# Schematic_3.net
KiCad netlist of a schematic drawn in Altium Designer
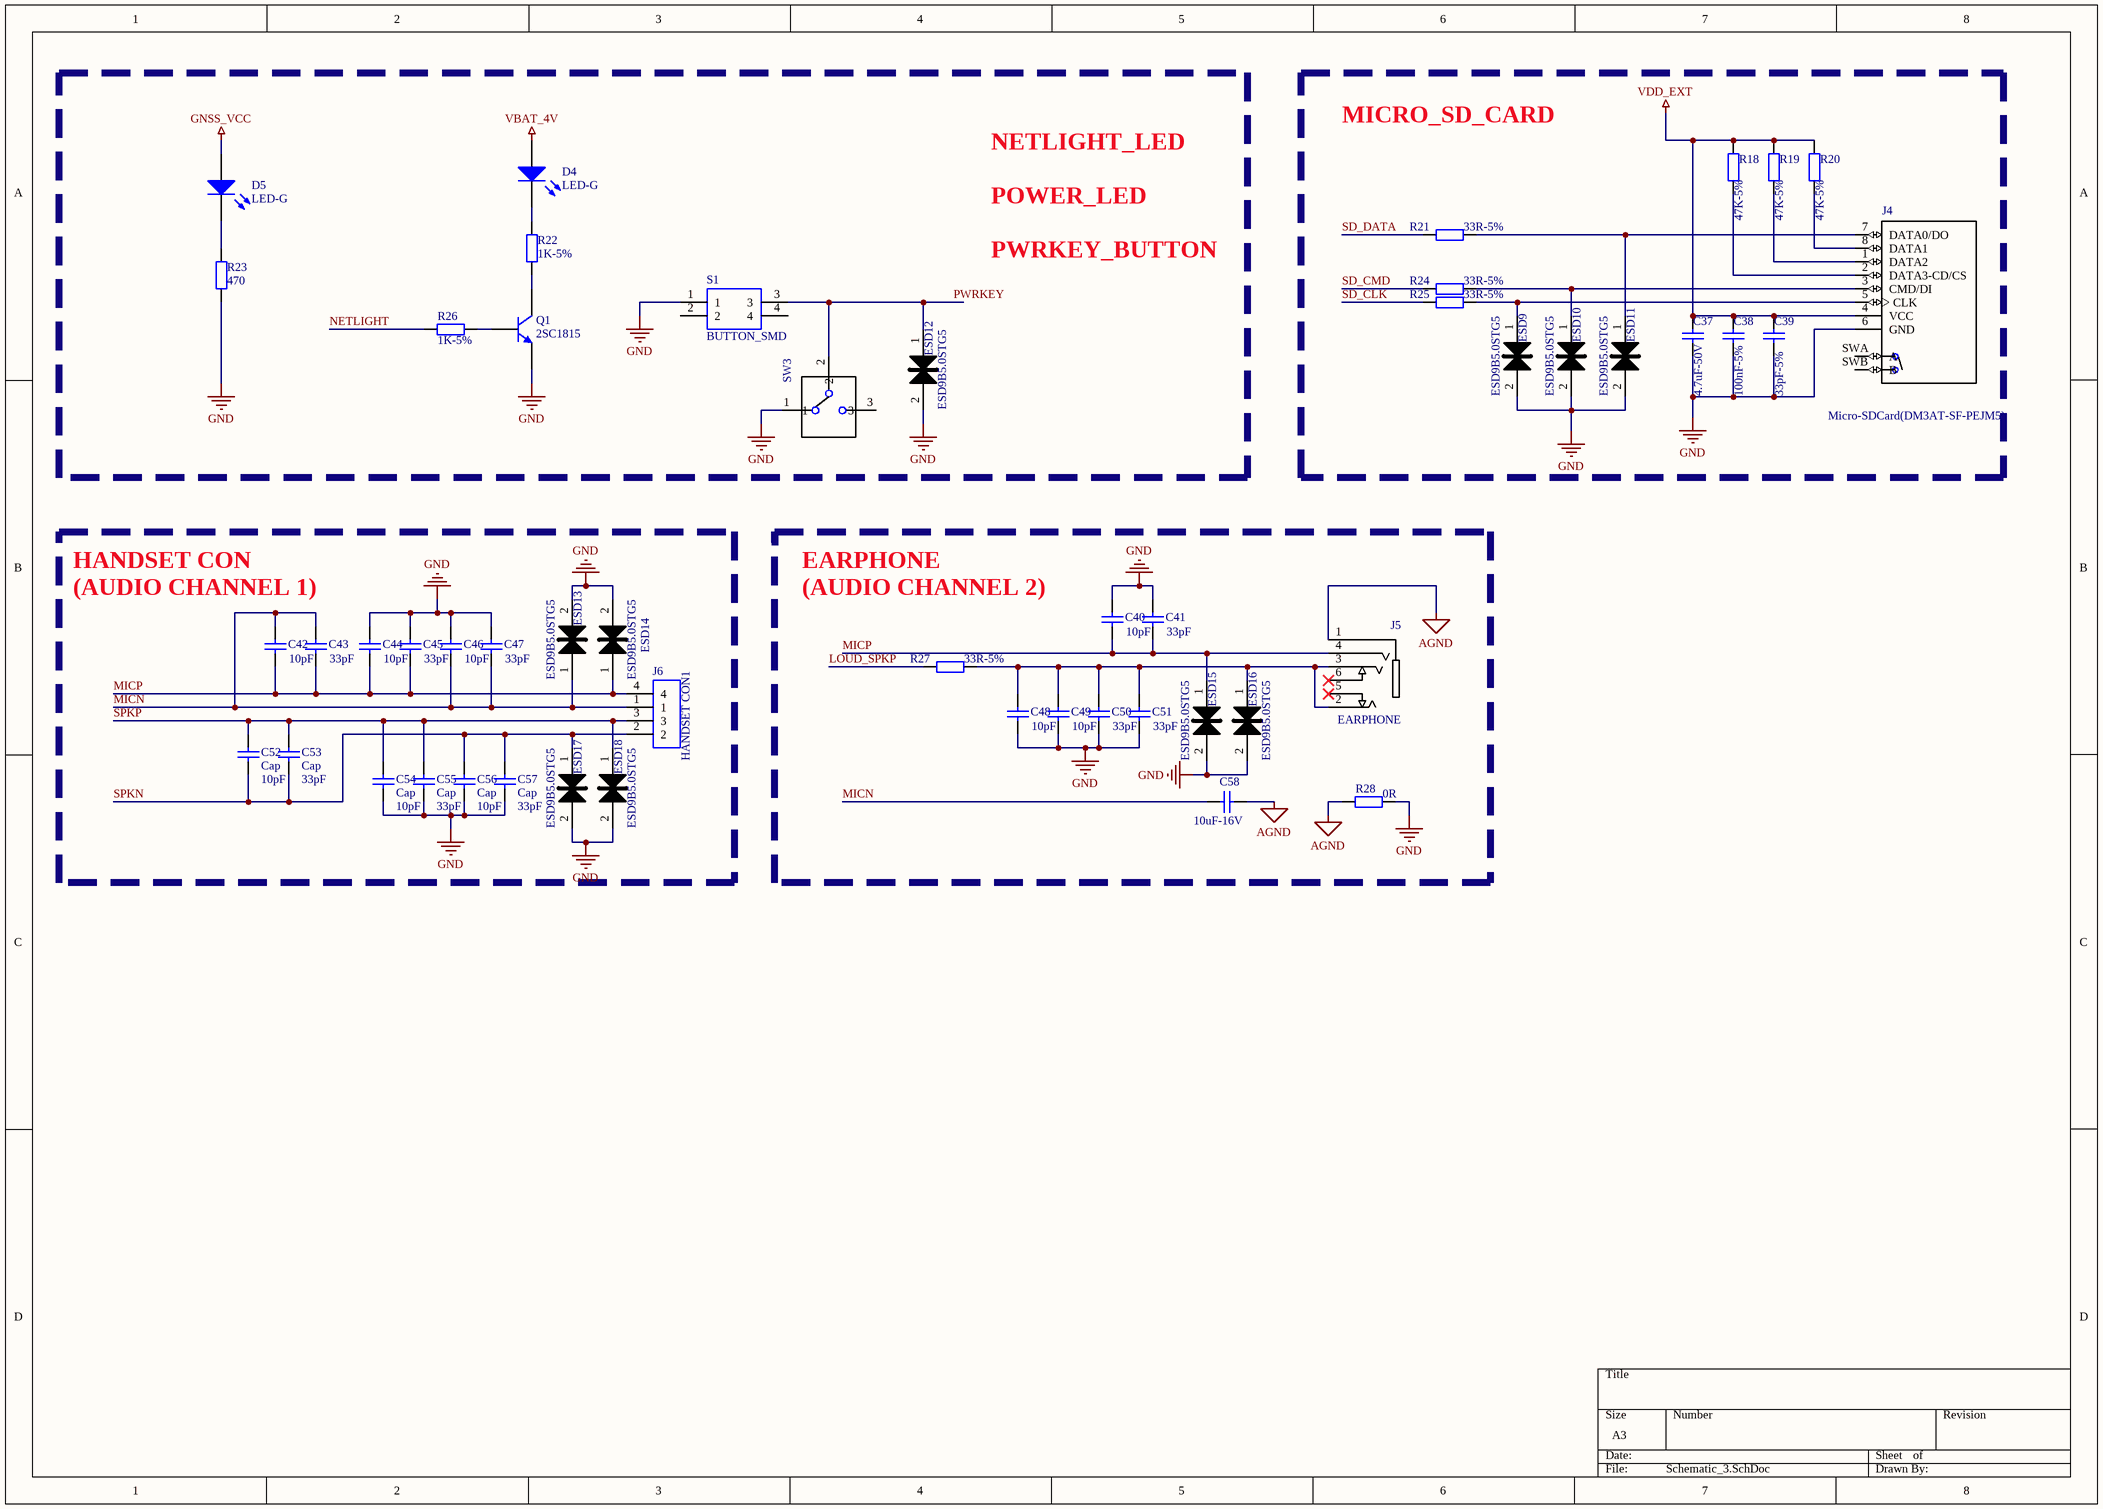
[diagram p0: Schematic_3.SchDoc]

(export (version "E")
  (design (tool "Eeschema 10.0.6"))
  (components
    (comp (ref "C37")
      (value "4.7uF-50V")
      (footprint "C0805")
      (description "Capacitor")
      (fields (field (name "Comment") "Cap") (field (name "PUBLISHER") "Altium Limited"))
      (libsource (lib "Miscellaneous Devices") (part "Cap"))
    )
    (comp (ref "C38")
      (value "100nF-5%")
      (footprint "C0805")
      (description "Capacitor")
      (fields (field (name "Comment") "Cap") (field (name "PUBLISHER") "Altium Limited"))
      (libsource (lib "Miscellaneous Devices") (part "Cap"))
    )
    (comp (ref "C39")
      (value "33pF-5%")
      (footprint "C0805")
      (description "Capacitor")
      (fields (field (name "Comment") "Cap") (field (name "PUBLISHER") "Altium Limited"))
      (libsource (lib "Miscellaneous Devices") (part "Cap"))
    )
    (comp (ref "C40")
      (value "10pF")
      (footprint "C0805")
      (description "Capacitor")
      (fields (field (name "Comment") "Cap") (field (name "PUBLISHER") "Altium Limited"))
      (libsource (lib "Miscellaneous Devices") (part "Cap"))
    )
    (comp (ref "C41")
      (value "33pF")
      (footprint "C0805")
      (description "Capacitor")
      (fields (field (name "Comment") "Cap") (field (name "PUBLISHER") "Altium Limited"))
      (libsource (lib "Miscellaneous Devices") (part "Cap"))
    )
    (comp (ref "C42")
      (value "10pF")
      (footprint "C0805")
      (description "Capacitor")
      (fields (field (name "Comment") "Cap") (field (name "PUBLISHER") "Altium Limited"))
      (libsource (lib "Miscellaneous Devices") (part "Cap"))
    )
    (comp (ref "C43")
      (value "33pF")
      (footprint "C0805")
      (description "Capacitor")
      (fields (field (name "Comment") "Cap") (field (name "PUBLISHER") "Altium Limited"))
      (libsource (lib "Miscellaneous Devices") (part "Cap"))
    )
    (comp (ref "C44")
      (value "10pF")
      (footprint "C0805")
      (description "Capacitor")
      (fields (field (name "Comment") "Cap") (field (name "PUBLISHER") "Altium Limited"))
      (libsource (lib "Miscellaneous Devices") (part "Cap"))
    )
    (comp (ref "C45")
      (value "33pF")
      (footprint "C0805")
      (description "Capacitor")
      (fields (field (name "Comment") "Cap") (field (name "PUBLISHER") "Altium Limited"))
      (libsource (lib "Miscellaneous Devices") (part "Cap"))
    )
    (comp (ref "C46")
      (value "10pF")
      (footprint "C0805")
      (description "Capacitor")
      (fields (field (name "Comment") "Cap") (field (name "PUBLISHER") "Altium Limited"))
      (libsource (lib "Miscellaneous Devices") (part "Cap"))
    )
    (comp (ref "C47")
      (value "33pF")
      (footprint "C0805")
      (description "Capacitor")
      (fields (field (name "Comment") "Cap") (field (name "PUBLISHER") "Altium Limited"))
      (libsource (lib "Miscellaneous Devices") (part "Cap"))
    )
    (comp (ref "C48")
      (value "10pF")
      (footprint "C0805")
      (description "Capacitor")
      (fields (field (name "Comment") "Cap") (field (name "PUBLISHER") "Altium Limited"))
      (libsource (lib "Miscellaneous Devices") (part "Cap"))
    )
    (comp (ref "C49")
      (value "10pF")
      (footprint "C0805")
      (description "Capacitor")
      (fields (field (name "Comment") "Cap") (field (name "PUBLISHER") "Altium Limited"))
      (libsource (lib "Miscellaneous Devices") (part "Cap"))
    )
    (comp (ref "C50")
      (value "33pF")
      (footprint "C0805")
      (description "Capacitor")
      (fields (field (name "Comment") "Cap") (field (name "PUBLISHER") "Altium Limited"))
      (libsource (lib "Miscellaneous Devices") (part "Cap"))
    )
    (comp (ref "C51")
      (value "33pF")
      (footprint "C0805")
      (description "Capacitor")
      (fields (field (name "Comment") "Cap") (field (name "PUBLISHER") "Altium Limited"))
      (libsource (lib "Miscellaneous Devices") (part "Cap"))
    )
    (comp (ref "C52")
      (value "Cap")
      (footprint "C0805")
      (description "Capacitor")
      (fields (field (name "ALTIUM_VALUE") "10pF") (field (name "PUBLISHER") "Altium Limited"))
      (libsource (lib "Miscellaneous Devices") (part "Cap"))
    )
    (comp (ref "C53")
      (value "Cap")
      (footprint "C0805")
      (description "Capacitor")
      (fields (field (name "ALTIUM_VALUE") "33pF") (field (name "PUBLISHER") "Altium Limited"))
      (libsource (lib "Miscellaneous Devices") (part "Cap"))
    )
    (comp (ref "C54")
      (value "Cap")
      (footprint "C0805")
      (description "Capacitor")
      (fields (field (name "ALTIUM_VALUE") "10pF") (field (name "PUBLISHER") "Altium Limited"))
      (libsource (lib "Miscellaneous Devices") (part "Cap"))
    )
    (comp (ref "C55")
      (value "Cap")
      (footprint "C0805")
      (description "Capacitor")
      (fields (field (name "ALTIUM_VALUE") "33pF") (field (name "PUBLISHER") "Altium Limited"))
      (libsource (lib "Miscellaneous Devices") (part "Cap"))
    )
    (comp (ref "C56")
      (value "Cap")
      (footprint "C0805")
      (description "Capacitor")
      (fields (field (name "ALTIUM_VALUE") "10pF") (field (name "PUBLISHER") "Altium Limited"))
      (libsource (lib "Miscellaneous Devices") (part "Cap"))
    )
    (comp (ref "C57")
      (value "Cap")
      (footprint "C0805")
      (description "Capacitor")
      (fields (field (name "ALTIUM_VALUE") "33pF") (field (name "PUBLISHER") "Altium Limited"))
      (libsource (lib "Miscellaneous Devices") (part "Cap"))
    )
    (comp (ref "C58")
      (value "10uF-16V")
      (footprint "C0805")
      (description "Capacitor")
      (fields (field (name "Comment") "Cap") (field (name "PUBLISHER") "Altium Limited"))
      (libsource (lib "Miscellaneous Devices") (part "Cap"))
    )
    (comp (ref "D4")
      (value "LED-G")
      (footprint "6-0805_L")
      (description "Typical INFRARED GaAs LED")
      (fields (field (name "PUBLISHER") "Altium Limited"))
      (libsource (lib "Miscellaneous Devices") (part "LED0"))
    )
    (comp (ref "D5")
      (value "LED-G")
      (footprint "6-0805_L")
      (description "Typical INFRARED GaAs LED")
      (fields (field (name "PUBLISHER") "Altium Limited"))
      (libsource (lib "Miscellaneous Devices") (part "LED0"))
    )
    (comp (ref "ESD9")
      (value "ESD9B5.0STG5")
      (footprint "ESD9B5.0STG5")
      (libsource (lib "ESD9B5") (part "1"))
    )
    (comp (ref "ESD10")
      (value "ESD9B5.0STG5")
      (footprint "ESD9B5.0STG5")
      (libsource (lib "ESD9B5") (part "1"))
    )
    (comp (ref "ESD11")
      (value "ESD9B5.0STG5")
      (footprint "ESD9B5.0STG5")
      (libsource (lib "ESD9B5") (part "1"))
    )
    (comp (ref "ESD12")
      (value "ESD9B5.0STG5")
      (footprint "ESD9B5.0STG5")
      (libsource (lib "ESD9B5") (part "1"))
    )
    (comp (ref "ESD13")
      (value "ESD9B5.0STG5")
      (footprint "ESD9B5.0STG5")
      (libsource (lib "ESD9B5") (part "1"))
    )
    (comp (ref "ESD14")
      (value "ESD9B5.0STG5")
      (footprint "ESD9B5.0STG5")
      (libsource (lib "ESD9B5") (part "1"))
    )
    (comp (ref "ESD15")
      (value "ESD9B5.0STG5")
      (footprint "ESD9B5.0STG5")
      (libsource (lib "ESD9B5") (part "1"))
    )
    (comp (ref "ESD16")
      (value "ESD9B5.0STG5")
      (footprint "ESD9B5.0STG5")
      (libsource (lib "ESD9B5") (part "1"))
    )
    (comp (ref "ESD17")
      (value "ESD9B5.0STG5")
      (footprint "ESD9B5.0STG5")
      (libsource (lib "ESD9B5") (part "1"))
    )
    (comp (ref "ESD18")
      (value "ESD9B5.0STG5")
      (footprint "ESD9B5.0STG5")
      (libsource (lib "ESD9B5") (part "1"))
    )
    (comp (ref "J4")
      (value "Micro-SDCard(DM3AT-SF-PEJM5)")
      (footprint "SD_CARD")
      (description "DM3 RA SMT microSD memory card push/push")
      (fields (field (name "MP") "DM3AT-SF-PEJM5") (field (name "MF") "Hirose"))
      (libsource (lib "DM3AT-SF-PEJM5") (part "DM3AT-SF-PEJM5"))
    )
    (comp (ref "J5")
      (value "EARPHONE")
      (footprint "Audio_Jack")
      (description "audio jack, 3.5 mm, rt, 4 conductor, mid mount SMT, 2 switches, T/R package")
      (fields (field (name "MF") "CUI") (field (name "MP") "SJ-43504-SMT-TR"))
      (libsource (lib "SJ-43504-SMT-TR") (part "SJ-43504-SMT-TR"))
    )
    (comp (ref "J6")
      (value "HANDSET CON1")
      (footprint "RJ11-HANDSETCON")
      (fields
        (field (name "MANUFACTURER_PART_NUMBER") "95009-7441")
        (field (name "RS PART NUMBER") "8967548")
      )
      (libsource (lib "95009-7441") (part "95009-7441"))
    )
    (comp (ref "Q1")
      (value "2SC1815")
      (footprint "SOT23_L")
      (description "NPN General Purpose Amplifier")
      (fields (field (name "PUBLISHER") "Altium Limited"))
      (libsource (lib "Miscellaneous Devices") (part "2N3904"))
    )
    (comp (ref "R18")
      (value "47K-5%")
      (footprint "6-0805_L")
      (description "Resistor")
      (fields (field (name "Comment") "Res2") (field (name "PUBLISHER") "Altium Limited"))
      (libsource (lib "Miscellaneous Devices") (part "Res2"))
    )
    (comp (ref "R19")
      (value "47K-5%")
      (footprint "6-0805_L")
      (description "Resistor")
      (fields (field (name "Comment") "Res2") (field (name "PUBLISHER") "Altium Limited"))
      (libsource (lib "Miscellaneous Devices") (part "Res2"))
    )
    (comp (ref "R20")
      (value "47K-5%")
      (footprint "6-0805_L")
      (description "Resistor")
      (fields (field (name "Comment") "Res2") (field (name "PUBLISHER") "Altium Limited"))
      (libsource (lib "Miscellaneous Devices") (part "Res2"))
    )
    (comp (ref "R21")
      (value "33R-5%")
      (footprint "6-0805_L")
      (description "Resistor")
      (fields (field (name "Comment") "Res2") (field (name "PUBLISHER") "Altium Limited"))
      (libsource (lib "") (part "Res2_1"))
    )
    (comp (ref "R22")
      (value "1K-5%")
      (footprint "6-0805_L")
      (description "Resistor")
      (fields (field (name "Comment") "Res2") (field (name "PUBLISHER") "Altium Limited"))
      (libsource (lib "") (part "Res2_2"))
    )
    (comp (ref "R23")
      (value "470")
      (footprint "6-0805_L")
      (description "Resistor")
      (fields (field (name "Comment") "Res2") (field (name "PUBLISHER") "Altium Limited"))
      (libsource (lib "") (part "Res2_2"))
    )
    (comp (ref "R24")
      (value "33R-5%")
      (footprint "6-0805_L")
      (description "Resistor")
      (fields (field (name "Comment") "Res2") (field (name "PUBLISHER") "Altium Limited"))
      (libsource (lib "") (part "Res2_1"))
    )
    (comp (ref "R25")
      (value "33R-5%")
      (footprint "6-0805_L")
      (description "Resistor")
      (fields (field (name "Comment") "Res2") (field (name "PUBLISHER") "Altium Limited"))
      (libsource (lib "") (part "Res2_1"))
    )
    (comp (ref "R26")
      (value "1K-5%")
      (footprint "6-0805_L")
      (description "Resistor")
      (fields (field (name "Comment") "Res2") (field (name "PUBLISHER") "Altium Limited"))
      (libsource (lib "") (part "Res2_3"))
    )
    (comp (ref "R27")
      (value "33R-5%")
      (footprint "6-0805_L")
      (description "Resistor")
      (fields (field (name "Comment") "Res2") (field (name "PUBLISHER") "Altium Limited"))
      (libsource (lib "") (part "Res2_1"))
    )
    (comp (ref "R28")
      (value "0R")
      (footprint "6-0805_L")
      (description "Resistor")
      (fields (field (name "Comment") "Res2") (field (name "PUBLISHER") "Altium Limited"))
      (libsource (lib "") (part "Res2_1"))
    )
    (comp (ref "S1")
      (value "BUTTON_SMD")
      (footprint "BUTTON_4PINS_SMD_3D")
      (description "6x6mm SMD tactile switch,5mm H 1.6N Black Button Tactile Switch, SPST-NO 0.05 A@ 12 V dc 1.4mm")
      (fields
        (field (name "MANUFACTURER_PART_NUMBER") "4-1437565-1")
        (field (name "RS PART NUMBER") "1616046")
      )
      (libsource (lib "4-1437565-1") (part "4-1437565-1"))
    )
    (comp (ref "SW3")
      (value "DIP-SLIDE-SWITCH(3P-11.6X4.0X5.4+2.0MM)")
      (footprint "SLIDE_SWITCH_3PINS")
      (description "EG Series SPDT On-On Vertical Through Hole Slide Switch")
      (fields (field (name "MF") "E-Switch") (field (name "MP") "EG1218"))
      (libsource (lib "DIP-SLIDE-SWITCH_3P-11.6X4.0X5.4_2.0MM_") (part "DIP-SLIDE-SWITCH(3P-11.6X4.0X5.4+2.0MM)"))
    )
  )
  (nets
    (net (code "1") (name "/LOUD_SPKP") (class "Default")
      (node (ref "R27") (pin "1") (pinfunction "1_1") (pintype "passive"))
    )
    (net (code "2") (name "/MICN") (class "Default")
      (node (ref "C42") (pin "2") (pinfunction "2_2") (pintype "passive"))
      (node (ref "C43") (pin "2") (pinfunction "2_2") (pintype "passive"))
      (node (ref "C46") (pin "1") (pinfunction "1_1") (pintype "passive"))
      (node (ref "C47") (pin "1") (pinfunction "1_1") (pintype "passive"))
      (node (ref "C58") (pin "1") (pinfunction "1_1") (pintype "passive"))
      (node (ref "ESD13") (pin "1") (pinfunction "A_1") (pintype "passive"))
      (node (ref "J6") (pin "1") (pinfunction "1_1") (pintype "passive"))
    )
    (net (code "3") (name "/MICP") (class "Default")
      (node (ref "C40") (pin "2") (pinfunction "2_2") (pintype "passive"))
      (node (ref "C41") (pin "2") (pinfunction "2_2") (pintype "passive"))
      (node (ref "C42") (pin "1") (pinfunction "1_1") (pintype "passive"))
      (node (ref "C43") (pin "1") (pinfunction "1_1") (pintype "passive"))
      (node (ref "C44") (pin "1") (pinfunction "1_1") (pintype "passive"))
      (node (ref "C45") (pin "1") (pinfunction "1_1") (pintype "passive"))
      (node (ref "ESD14") (pin "1") (pinfunction "A_1") (pintype "passive"))
      (node (ref "ESD15") (pin "1") (pinfunction "A_1") (pintype "passive"))
      (node (ref "J5") (pin "4") (pinfunction "RING2_4") (pintype "passive"))
      (node (ref "J6") (pin "4") (pinfunction "4_4") (pintype "passive"))
    )
    (net (code "4") (name "/NETLIGHT") (class "Default")
      (node (ref "R26") (pin "2") (pinfunction "2_2") (pintype "passive"))
    )
    (net (code "5") (name "/PWRKEY") (class "Default")
      (node (ref "ESD12") (pin "1") (pinfunction "A_1") (pintype "passive"))
      (node (ref "S1") (pin "3") (pinfunction "3_3") (pintype "passive"))
      (node (ref "SW3") (pin "2") (pinfunction "2_2") (pintype "bidirectional"))
    )
    (net (code "6") (name "/SD_CLK") (class "Default")
      (node (ref "R25") (pin "1") (pinfunction "1_1") (pintype "passive"))
    )
    (net (code "7") (name "/SD_CMD") (class "Default")
      (node (ref "R24") (pin "1") (pinfunction "1_1") (pintype "passive"))
    )
    (net (code "8") (name "/SD_DATA") (class "Default")
      (node (ref "R21") (pin "1") (pinfunction "1_1") (pintype "passive"))
    )
    (net (code "9") (name "/SPKN") (class "Default")
      (node (ref "C52") (pin "1") (pinfunction "1_1") (pintype "passive"))
      (node (ref "C53") (pin "1") (pinfunction "1_1") (pintype "passive"))
      (node (ref "C56") (pin "2") (pinfunction "2_2") (pintype "passive"))
      (node (ref "C57") (pin "2") (pinfunction "2_2") (pintype "passive"))
      (node (ref "ESD17") (pin "1") (pinfunction "A_1") (pintype "passive"))
      (node (ref "J6") (pin "2") (pinfunction "2_2") (pintype "passive"))
    )
    (net (code "10") (name "/SPKP") (class "Default")
      (node (ref "C52") (pin "2") (pinfunction "2_2") (pintype "passive"))
      (node (ref "C53") (pin "2") (pinfunction "2_2") (pintype "passive"))
      (node (ref "C54") (pin "2") (pinfunction "2_2") (pintype "passive"))
      (node (ref "C55") (pin "2") (pinfunction "2_2") (pintype "passive"))
      (node (ref "ESD18") (pin "1") (pinfunction "A_1") (pintype "passive"))
      (node (ref "J6") (pin "3") (pinfunction "3_3") (pintype "passive"))
    )
    (net (code "11") (name "AGND") (class "Default")
      (node (ref "C58") (pin "2") (pinfunction "2_2") (pintype "passive"))
      (node (ref "J5") (pin "1") (pinfunction "SLEEVE_1") (pintype "passive"))
      (node (ref "R28") (pin "1") (pinfunction "1_1") (pintype "passive"))
    )
    (net (code "12") (name "GND") (class "Default")
      (node (ref "C37") (pin "1") (pinfunction "1_1") (pintype "passive"))
      (node (ref "C38") (pin "1") (pinfunction "1_1") (pintype "passive"))
      (node (ref "C39") (pin "2") (pinfunction "2_2") (pintype "passive"))
      (node (ref "C40") (pin "1") (pinfunction "1_1") (pintype "passive"))
      (node (ref "C41") (pin "1") (pinfunction "1_1") (pintype "passive"))
      (node (ref "C44") (pin "2") (pinfunction "2_2") (pintype "passive"))
      (node (ref "C45") (pin "2") (pinfunction "2_2") (pintype "passive"))
      (node (ref "C46") (pin "2") (pinfunction "2_2") (pintype "passive"))
      (node (ref "C47") (pin "2") (pinfunction "2_2") (pintype "passive"))
      (node (ref "C48") (pin "1") (pinfunction "1_1") (pintype "passive"))
      (node (ref "C49") (pin "1") (pinfunction "1_1") (pintype "passive"))
      (node (ref "C50") (pin "1") (pinfunction "1_1") (pintype "passive"))
      (node (ref "C51") (pin "1") (pinfunction "1_1") (pintype "passive"))
      (node (ref "C54") (pin "1") (pinfunction "1_1") (pintype "passive"))
      (node (ref "C55") (pin "1") (pinfunction "1_1") (pintype "passive"))
      (node (ref "C56") (pin "1") (pinfunction "1_1") (pintype "passive"))
      (node (ref "C57") (pin "1") (pinfunction "1_1") (pintype "passive"))
      (node (ref "ESD10") (pin "2") (pinfunction "K_2") (pintype "passive"))
      (node (ref "ESD11") (pin "2") (pinfunction "K_2") (pintype "passive"))
      (node (ref "ESD12") (pin "2") (pinfunction "K_2") (pintype "passive"))
      (node (ref "ESD13") (pin "2") (pinfunction "K_2") (pintype "passive"))
      (node (ref "ESD14") (pin "2") (pinfunction "K_2") (pintype "passive"))
      (node (ref "ESD15") (pin "2") (pinfunction "K_2") (pintype "passive"))
      (node (ref "ESD16") (pin "2") (pinfunction "K_2") (pintype "passive"))
      (node (ref "ESD17") (pin "2") (pinfunction "K_2") (pintype "passive"))
      (node (ref "ESD18") (pin "2") (pinfunction "K_2") (pintype "passive"))
      (node (ref "ESD9") (pin "2") (pinfunction "K_2") (pintype "passive"))
      (node (ref "J4") (pin "6") (pinfunction "GND_6") (pintype "power_in"))
      (node (ref "Q1") (pin "1") (pinfunction "E_1") (pintype "passive"))
      (node (ref "R23") (pin "2") (pinfunction "2_2") (pintype "passive"))
      (node (ref "R28") (pin "2") (pinfunction "2_2") (pintype "passive"))
      (node (ref "S1") (pin "1") (pinfunction "1_1") (pintype "passive"))
      (node (ref "SW3") (pin "1") (pinfunction "1_1") (pintype "bidirectional"))
    )
    (net (code "13") (name "GNSS_VCC") (class "Default")
      (node (ref "D5") (pin "1") (pinfunction "A_1") (pintype "passive"))
    )
    (net (code "14") (name "Net-(D4-K)") (class "Default")
      (node (ref "D4") (pin "2") (pinfunction "K_2") (pintype "passive"))
      (node (ref "R22") (pin "1") (pinfunction "1_1") (pintype "passive"))
    )
    (net (code "15") (name "Net-(D5-K)") (class "Default")
      (node (ref "D5") (pin "2") (pinfunction "K_2") (pintype "passive"))
      (node (ref "R23") (pin "1") (pinfunction "1_1") (pintype "passive"))
    )
    (net (code "16") (name "Net-(ESD9-A)") (class "Default")
      (node (ref "ESD9") (pin "1") (pinfunction "A_1") (pintype "passive"))
      (node (ref "J4") (pin "5") (pinfunction "CLK_5") (pintype "bidirectional"))
      (node (ref "R25") (pin "2") (pinfunction "2_2") (pintype "passive"))
    )
    (net (code "17") (name "Net-(ESD10-A)") (class "Default")
      (node (ref "ESD10") (pin "1") (pinfunction "A_1") (pintype "passive"))
      (node (ref "J4") (pin "3") (pinfunction "CMD/DI_3") (pintype "bidirectional"))
      (node (ref "R24") (pin "2") (pinfunction "2_2") (pintype "passive"))
    )
    (net (code "18") (name "Net-(ESD11-A)") (class "Default")
      (node (ref "ESD11") (pin "1") (pinfunction "A_1") (pintype "passive"))
      (node (ref "J4") (pin "7") (pinfunction "DATA0/DO_7") (pintype "bidirectional"))
      (node (ref "R21") (pin "2") (pinfunction "2_2") (pintype "passive"))
    )
    (net (code "19") (name "Net-(ESD16-A)") (class "Default")
      (node (ref "C48") (pin "2") (pinfunction "2_2") (pintype "passive"))
      (node (ref "C49") (pin "2") (pinfunction "2_2") (pintype "passive"))
      (node (ref "C50") (pin "2") (pinfunction "2_2") (pintype "passive"))
      (node (ref "C51") (pin "2") (pinfunction "2_2") (pintype "passive"))
      (node (ref "ESD16") (pin "1") (pinfunction "A_1") (pintype "passive"))
      (node (ref "J5") (pin "2") (pinfunction "TIP_2") (pintype "passive"))
      (node (ref "J5") (pin "3") (pinfunction "RING1_3") (pintype "passive"))
      (node (ref "R27") (pin "2") (pinfunction "2_2") (pintype "passive"))
    )
    (net (code "20") (name "Net-(J4-DATA1)") (class "Default")
      (node (ref "J4") (pin "8") (pinfunction "DATA1_8") (pintype "bidirectional"))
      (node (ref "R20") (pin "1") (pinfunction "1_1") (pintype "passive"))
    )
    (net (code "21") (name "Net-(J4-DATA2)") (class "Default")
      (node (ref "J4") (pin "1") (pinfunction "DATA2_1") (pintype "bidirectional"))
      (node (ref "R19") (pin "1") (pinfunction "1_1") (pintype "passive"))
    )
    (net (code "22") (name "Net-(J4-DATA3-CD{slash}CS)") (class "Default")
      (node (ref "J4") (pin "2") (pinfunction "DATA3-CD/CS_2") (pintype "bidirectional"))
      (node (ref "R18") (pin "1") (pinfunction "1_1") (pintype "passive"))
    )
    (net (code "23") (name "Net-(Q1-B)") (class "Default")
      (node (ref "Q1") (pin "2") (pinfunction "B_2") (pintype "passive"))
      (node (ref "R26") (pin "1") (pinfunction "1_1") (pintype "passive"))
    )
    (net (code "24") (name "Net-(Q1-C)") (class "Default")
      (node (ref "Q1") (pin "3") (pinfunction "C_3") (pintype "passive"))
      (node (ref "R22") (pin "2") (pinfunction "2_2") (pintype "passive"))
    )
    (net (code "25") (name "VBAT_4V") (class "Default")
      (node (ref "D4") (pin "1") (pinfunction "A_1") (pintype "passive"))
    )
    (net (code "26") (name "VDD_EXT") (class "Default")
      (node (ref "C37") (pin "2") (pinfunction "2_2") (pintype "passive"))
      (node (ref "C38") (pin "2") (pinfunction "2_2") (pintype "passive"))
      (node (ref "C39") (pin "1") (pinfunction "1_1") (pintype "passive"))
      (node (ref "J4") (pin "4") (pinfunction "VCC_4") (pintype "power_in"))
      (node (ref "R18") (pin "2") (pinfunction "2_2") (pintype "passive"))
      (node (ref "R19") (pin "2") (pinfunction "2_2") (pintype "passive"))
      (node (ref "R20") (pin "2") (pinfunction "2_2") (pintype "passive"))
    )
    (net (code "27") (name "unconnected-(J4-A-PadSWA)") (class "Default")
      (node (ref "J4") (pin "SWA") (pinfunction "A_SWA") (pintype "bidirectional"))
    )
    (net (code "28") (name "unconnected-(J4-B-PadSWB)") (class "Default")
      (node (ref "J4") (pin "SWB") (pinfunction "B_SWB") (pintype "bidirectional"))
    )
    (net (code "29") (name "unconnected-(J5-RING1_SWITCH-Pad6)") (class "Default")
      (node (ref "J5") (pin "6") (pinfunction "RING1_SWITCH_6") (pintype "passive+no_connect"))
    )
    (net (code "30") (name "unconnected-(J5-TIP_SWITCH-Pad5)") (class "Default")
      (node (ref "J5") (pin "5") (pinfunction "TIP_SWITCH_5") (pintype "passive+no_connect"))
    )
    (net (code "31") (name "unconnected-(S1-Pad2)") (class "Default")
      (node (ref "S1") (pin "2") (pinfunction "2_2") (pintype "passive"))
    )
    (net (code "32") (name "unconnected-(S1-Pad4)") (class "Default")
      (node (ref "S1") (pin "4") (pinfunction "4_4") (pintype "passive"))
    )
    (net (code "33") (name "unconnected-(SW3-Pad3)") (class "Default")
      (node (ref "SW3") (pin "3") (pinfunction "3_3") (pintype "bidirectional"))
    )
  )
)
